# Draft_2.net
KiCad netlist of a schematic drawn in EAGLE
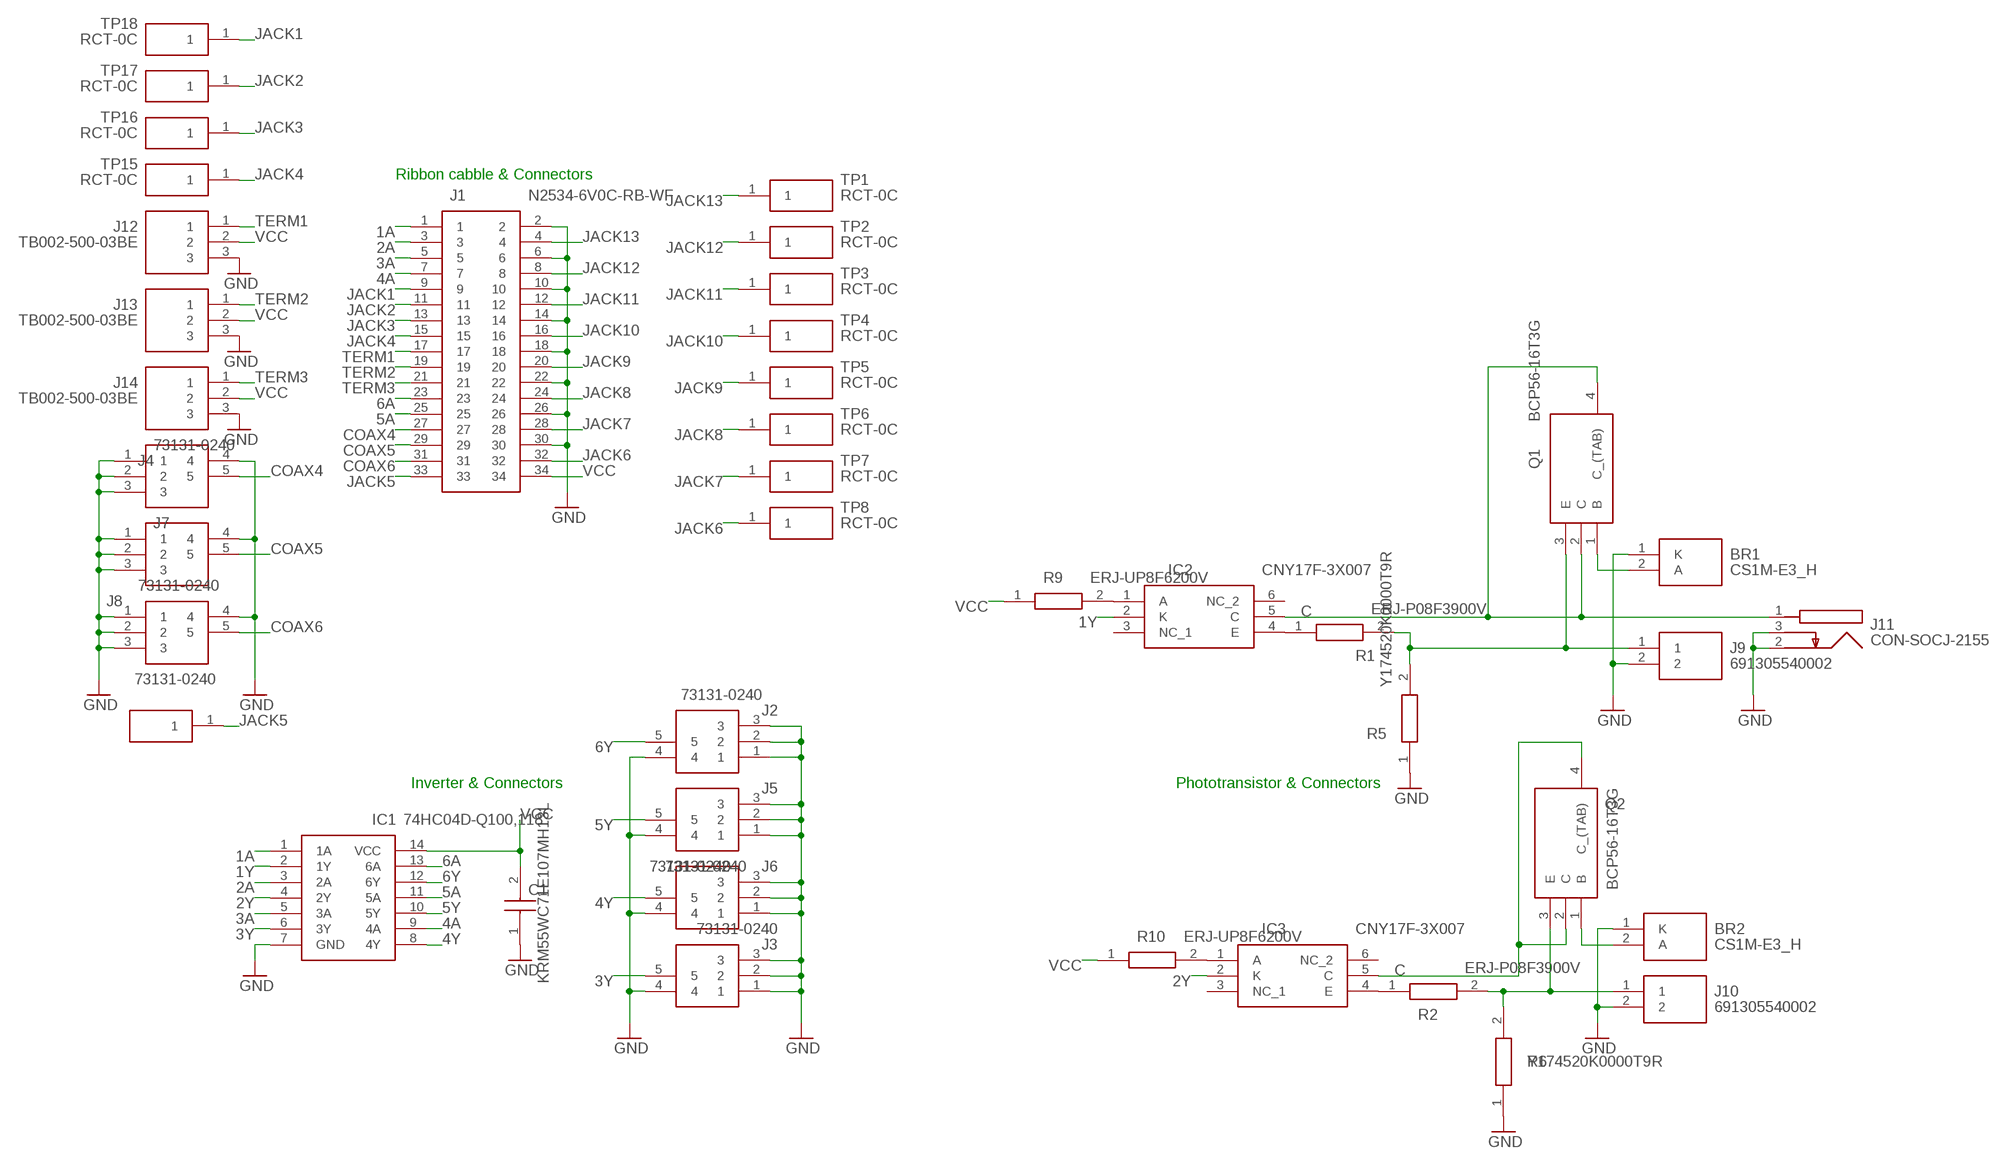
[diagram p0: schematic, sheet 1]

(export (version "E")
  (design (tool "Eeschema 10.0.6"))
  (components
    (comp (ref "BR1")
      (value "CS1M-E3_H")
      (footprint "eagle-import:DIOM5127X229N")
      (fields
        (field (name "MANUFACTURER_PART_NUMBER") "CS1M-E3/H")
        (field (name "MOUSER_PART_NUMBER") "78-CS1M-E3/H")
      )
      (libsource (lib "eagle-import") (part "CS1M-E3_H"))
    )
    (comp (ref "BR2")
      (value "CS1M-E3_H")
      (footprint "eagle-import:DIOM5127X229N")
      (fields
        (field (name "MANUFACTURER_PART_NUMBER") "CS1M-E3/H")
        (field (name "MOUSER_PART_NUMBER") "78-CS1M-E3/H")
      )
      (libsource (lib "eagle-import") (part "CS1M-E3_H"))
    )
    (comp (ref "C1")
      (value "KRM55WC71E107MH13L")
      (footprint "eagle-import:CAPC6153X670N")
      (fields (field (name "MOUSER_PART_NUMBER") "81-KRM55WC71E107MH3L"))
      (libsource (lib "eagle-import") (part "KRM55WC71E107MH13L"))
    )
    (comp (ref "IC1")
      (value "74HC04D-Q100,118")
      (footprint "eagle-import:SOIC127P600X175-14N")
      (fields (field (name "MOUSER_PART_NUMBER") "771-74HC04D-Q100"))
      (libsource (lib "eagle-import") (part "74HC04D-Q100,118"))
    )
    (comp (ref "IC2")
      (value "CNY17F-3X007")
      (footprint "eagle-import:SOP254P1030X440-6N")
      (fields (field (name "MOUSER_PART_NUMBER") "782-CNY17F-3X007"))
      (libsource (lib "eagle-import") (part "CNY17F-3X007"))
    )
    (comp (ref "IC3")
      (value "CNY17F-3X007")
      (footprint "eagle-import:SOP254P1030X440-6N")
      (fields (field (name "MOUSER_PART_NUMBER") "782-CNY17F-3X007"))
      (libsource (lib "eagle-import") (part "CNY17F-3X007"))
    )
    (comp (ref "J1")
      (value "N2534-6V0C-RB-WF")
      (footprint "eagle-import:3M_N2534-6V0C-RB-WF")
      (fields
        (field (name "MOUSER_PART_NUMBER") "517-N2534-6V0C-RB-WF")
        (field (name "RS_PART_NUMBER") "0212650")
      )
      (libsource (lib "eagle-import") (part "N2534-6V0C-RB-WF"))
    )
    (comp (ref "J2")
      (value "73131-0240")
      (footprint "eagle-import:731310240")
      (fields (field (name "MOUSER_PART_NUMBER") "538-73131-0240"))
      (libsource (lib "eagle-import") (part "73131-0240"))
    )
    (comp (ref "J3")
      (value "73131-0240")
      (footprint "eagle-import:731310240")
      (fields (field (name "MOUSER_PART_NUMBER") "538-73131-0240"))
      (libsource (lib "eagle-import") (part "73131-0240"))
    )
    (comp (ref "J4")
      (value "73131-0240")
      (footprint "eagle-import:731310240")
      (fields (field (name "MOUSER_PART_NUMBER") "538-73131-0240"))
      (libsource (lib "eagle-import") (part "73131-0240"))
    )
    (comp (ref "J5")
      (value "73131-0240")
      (footprint "eagle-import:731310240")
      (fields (field (name "MOUSER_PART_NUMBER") "538-73131-0240"))
      (libsource (lib "eagle-import") (part "73131-0240"))
    )
    (comp (ref "J6")
      (value "73131-0240")
      (footprint "eagle-import:731310240")
      (fields (field (name "MOUSER_PART_NUMBER") "538-73131-0240"))
      (libsource (lib "eagle-import") (part "73131-0240"))
    )
    (comp (ref "J7")
      (value "73131-0240")
      (footprint "eagle-import:731310240")
      (fields (field (name "MOUSER_PART_NUMBER") "538-73131-0240"))
      (libsource (lib "eagle-import") (part "73131-0240"))
    )
    (comp (ref "J8")
      (value "73131-0240")
      (footprint "eagle-import:731310240")
      (fields (field (name "MOUSER_PART_NUMBER") "538-73131-0240"))
      (libsource (lib "eagle-import") (part "73131-0240"))
    )
    (comp (ref "J9")
      (value "691305540002")
      (footprint "eagle-import:SHDRRA2W100P0X508_1X2_1216X120")
      (fields (field (name "MOUSER_PART_NUMBER") "710-691305540002"))
      (libsource (lib "eagle-import") (part "691305540002"))
    )
    (comp (ref "J10")
      (value "691305540002")
      (footprint "eagle-import:SHDRRA2W100P0X508_1X2_1216X120")
      (fields (field (name "MOUSER_PART_NUMBER") "710-691305540002"))
      (libsource (lib "eagle-import") (part "691305540002"))
    )
    (comp (ref "J11")
      (value "CON-SOCJ-2155")
      (footprint "eagle-import:CONSOCJ2155")
      (fields (field (name "MOUSER_PART_NUMBER") "992-CON-SOCJ-2155"))
      (libsource (lib "eagle-import") (part "CON-SOCJ-2155"))
    )
    (comp (ref "J12")
      (value "TB002-500-03BE")
      (footprint "eagle-import:SHDR3W100P0X500_1X3_1500X760X1")
      (fields (field (name "MOUSER_PART_NUMBER") "490-TB002-500-03BE"))
      (libsource (lib "eagle-import") (part "TB002-500-03BE"))
    )
    (comp (ref "J13")
      (value "TB002-500-03BE")
      (footprint "eagle-import:SHDR3W100P0X500_1X3_1500X760X1")
      (fields (field (name "MOUSER_PART_NUMBER") "490-TB002-500-03BE"))
      (libsource (lib "eagle-import") (part "TB002-500-03BE"))
    )
    (comp (ref "J14")
      (value "TB002-500-03BE")
      (footprint "eagle-import:SHDR3W100P0X500_1X3_1500X760X1")
      (fields (field (name "MOUSER_PART_NUMBER") "490-TB002-500-03BE"))
      (libsource (lib "eagle-import") (part "TB002-500-03BE"))
    )
    (comp (ref "Q1")
      (value "BCP56-16T3G")
      (footprint "eagle-import:SOT230P700X175-4N")
      (fields
        (field (name "MOUSER_PART_NUMBER") "863-BCP56-16T3G")
        (field (name "RS_PART_NUMBER") "7737633P")
      )
      (libsource (lib "eagle-import") (part "BCP56-16T3G"))
    )
    (comp (ref "Q2")
      (value "BCP56-16T3G")
      (footprint "eagle-import:SOT230P700X175-4N")
      (fields
        (field (name "MOUSER_PART_NUMBER") "863-BCP56-16T3G")
        (field (name "RS_PART_NUMBER") "7737633P")
      )
      (libsource (lib "eagle-import") (part "BCP56-16T3G"))
    )
    (comp (ref "R1")
      (value "ERJ-P08F3900V")
      (footprint "eagle-import:RESC3116X70N")
      (fields (field (name "MOUSER_PART_NUMBER") "667-ERJ-P08F3900V"))
      (libsource (lib "eagle-import") (part "ERJ-P08F3900V"))
    )
    (comp (ref "R2")
      (value "ERJ-P08F3900V")
      (footprint "eagle-import:RESC3116X70N")
      (fields (field (name "MOUSER_PART_NUMBER") "667-ERJ-P08F3900V"))
      (libsource (lib "eagle-import") (part "ERJ-P08F3900V"))
    )
    (comp (ref "R5")
      (value "Y174520K0000T9R")
      (footprint "eagle-import:RESM6032X279N")
      (fields
        (field (name "MOUSER_PART_NUMBER") "71-SMR1DZ20K000TST")
        (field (name "RS_PART_NUMBER") "7637249P")
      )
      (libsource (lib "eagle-import") (part "Y174520K0000T9R"))
    )
    (comp (ref "R6")
      (value "Y174520K0000T9R")
      (footprint "eagle-import:RESM6032X279N")
      (fields
        (field (name "MOUSER_PART_NUMBER") "71-SMR1DZ20K000TST")
        (field (name "RS_PART_NUMBER") "7637249P")
      )
      (libsource (lib "eagle-import") (part "Y174520K0000T9R"))
    )
    (comp (ref "R9")
      (value "ERJ-UP8F6200V")
      (footprint "eagle-import:RESC3116X70N")
      (fields (field (name "MOUSER_PART_NUMBER") "667-ERJ-UP8F6200V"))
      (libsource (lib "eagle-import") (part "ERJ-UP8F6200V"))
    )
    (comp (ref "R10")
      (value "ERJ-UP8F6200V")
      (footprint "eagle-import:RESC3116X70N")
      (fields (field (name "MOUSER_PART_NUMBER") "667-ERJ-UP8F6200V"))
      (libsource (lib "eagle-import") (part "ERJ-UP8F6200V"))
    )
    (comp (ref "TP1")
      (value "RCT-0C")
      (footprint "eagle-import:RCT-0C")
      (fields (field (name "MOUSER_PART_NUMBER") "279-RCT-0C"))
      (libsource (lib "eagle-import") (part "RCT-0C"))
    )
    (comp (ref "TP2")
      (value "RCT-0C")
      (footprint "eagle-import:RCT-0C")
      (fields (field (name "MOUSER_PART_NUMBER") "279-RCT-0C"))
      (libsource (lib "eagle-import") (part "RCT-0C"))
    )
    (comp (ref "TP3")
      (value "RCT-0C")
      (footprint "eagle-import:RCT-0C")
      (fields (field (name "MOUSER_PART_NUMBER") "279-RCT-0C"))
      (libsource (lib "eagle-import") (part "RCT-0C"))
    )
    (comp (ref "TP4")
      (value "RCT-0C")
      (footprint "eagle-import:RCT-0C")
      (fields (field (name "MOUSER_PART_NUMBER") "279-RCT-0C"))
      (libsource (lib "eagle-import") (part "RCT-0C"))
    )
    (comp (ref "TP5")
      (value "RCT-0C")
      (footprint "eagle-import:RCT-0C")
      (fields (field (name "MOUSER_PART_NUMBER") "279-RCT-0C"))
      (libsource (lib "eagle-import") (part "RCT-0C"))
    )
    (comp (ref "TP6")
      (value "RCT-0C")
      (footprint "eagle-import:RCT-0C")
      (fields (field (name "MOUSER_PART_NUMBER") "279-RCT-0C"))
      (libsource (lib "eagle-import") (part "RCT-0C"))
    )
    (comp (ref "TP7")
      (value "RCT-0C")
      (footprint "eagle-import:RCT-0C")
      (fields (field (name "MOUSER_PART_NUMBER") "279-RCT-0C"))
      (libsource (lib "eagle-import") (part "RCT-0C"))
    )
    (comp (ref "TP8")
      (value "RCT-0C")
      (footprint "eagle-import:RCT-0C")
      (fields (field (name "MOUSER_PART_NUMBER") "279-RCT-0C"))
      (libsource (lib "eagle-import") (part "RCT-0C"))
    )
    (comp (ref "TP9")
      (value "RCT-0C")
      (footprint "eagle-import:RCT-0C")
      (fields (field (name "MOUSER_PART_NUMBER") "279-RCT-0C"))
      (libsource (lib "eagle-import") (part "RCT-0C"))
    )
    (comp (ref "TP15")
      (value "RCT-0C")
      (footprint "eagle-import:RCT-0C")
      (fields (field (name "MOUSER_PART_NUMBER") "279-RCT-0C"))
      (libsource (lib "eagle-import") (part "RCT-0C"))
    )
    (comp (ref "TP16")
      (value "RCT-0C")
      (footprint "eagle-import:RCT-0C")
      (fields (field (name "MOUSER_PART_NUMBER") "279-RCT-0C"))
      (libsource (lib "eagle-import") (part "RCT-0C"))
    )
    (comp (ref "TP17")
      (value "RCT-0C")
      (footprint "eagle-import:RCT-0C")
      (fields (field (name "MOUSER_PART_NUMBER") "279-RCT-0C"))
      (libsource (lib "eagle-import") (part "RCT-0C"))
    )
    (comp (ref "TP18")
      (value "RCT-0C")
      (footprint "eagle-import:RCT-0C")
      (fields (field (name "MOUSER_PART_NUMBER") "279-RCT-0C"))
      (libsource (lib "eagle-import") (part "RCT-0C"))
    )
  )
  (nets
    (net (code "1") (name "/1A") (class "Default")
      (node (ref "IC1") (pin "1") (pinfunction "1A_1") (pintype "bidirectional"))
      (node (ref "J1") (pin "1") (pinfunction "1_1") (pintype "bidirectional"))
    )
    (net (code "2") (name "/1Y") (class "Default")
      (node (ref "IC1") (pin "2") (pinfunction "1Y_2") (pintype "bidirectional"))
      (node (ref "IC2") (pin "2") (pinfunction "K_2") (pintype "bidirectional"))
    )
    (net (code "3") (name "/2A") (class "Default")
      (node (ref "IC1") (pin "3") (pinfunction "2A_3") (pintype "bidirectional"))
      (node (ref "J1") (pin "3") (pinfunction "3_3") (pintype "bidirectional"))
    )
    (net (code "4") (name "/2Y") (class "Default")
      (node (ref "IC1") (pin "4") (pinfunction "2Y_4") (pintype "bidirectional"))
      (node (ref "IC3") (pin "2") (pinfunction "K_2") (pintype "bidirectional"))
    )
    (net (code "5") (name "/3A") (class "Default")
      (node (ref "IC1") (pin "5") (pinfunction "3A_5") (pintype "bidirectional"))
      (node (ref "J1") (pin "5") (pinfunction "5_5") (pintype "bidirectional"))
    )
    (net (code "6") (name "/3Y") (class "Default")
      (node (ref "IC1") (pin "6") (pinfunction "3Y_6") (pintype "bidirectional"))
      (node (ref "J3") (pin "5") (pinfunction "5_5") (pintype "bidirectional"))
    )
    (net (code "7") (name "/4A") (class "Default")
      (node (ref "IC1") (pin "9") (pinfunction "4A_9") (pintype "bidirectional"))
      (node (ref "J1") (pin "7") (pinfunction "7_7") (pintype "bidirectional"))
    )
    (net (code "8") (name "/4Y") (class "Default")
      (node (ref "IC1") (pin "8") (pinfunction "4Y_8") (pintype "bidirectional"))
      (node (ref "J6") (pin "5") (pinfunction "5_5") (pintype "bidirectional"))
    )
    (net (code "9") (name "/5A") (class "Default")
      (node (ref "IC1") (pin "11") (pinfunction "5A_11") (pintype "bidirectional"))
      (node (ref "J1") (pin "25") (pinfunction "25_25") (pintype "bidirectional"))
    )
    (net (code "10") (name "/5Y") (class "Default")
      (node (ref "IC1") (pin "10") (pinfunction "5Y_10") (pintype "bidirectional"))
      (node (ref "J5") (pin "5") (pinfunction "5_5") (pintype "bidirectional"))
    )
    (net (code "11") (name "/6A") (class "Default")
      (node (ref "IC1") (pin "13") (pinfunction "6A_13") (pintype "bidirectional"))
      (node (ref "J1") (pin "23") (pinfunction "23_23") (pintype "bidirectional"))
    )
    (net (code "12") (name "/6Y") (class "Default")
      (node (ref "IC1") (pin "12") (pinfunction "6Y_12") (pintype "bidirectional"))
      (node (ref "J2") (pin "5") (pinfunction "5_5") (pintype "bidirectional"))
    )
    (net (code "13") (name "/C") (class "Default")
      (node (ref "IC2") (pin "5") (pinfunction "C_5") (pintype "bidirectional"))
      (node (ref "IC3") (pin "5") (pinfunction "C_5") (pintype "bidirectional"))
      (node (ref "J11") (pin "1") (pinfunction "1_1") (pintype "bidirectional"))
      (node (ref "Q1") (pin "2") (pinfunction "C_2") (pintype "bidirectional"))
      (node (ref "Q1") (pin "4") (pinfunction "C_(TAB)_4") (pintype "bidirectional"))
      (node (ref "Q2") (pin "2") (pinfunction "C_2") (pintype "bidirectional"))
      (node (ref "Q2") (pin "4") (pinfunction "C_(TAB)_4") (pintype "bidirectional"))
    )
    (net (code "14") (name "/COAX4") (class "Default")
      (node (ref "J1") (pin "27") (pinfunction "27_27") (pintype "bidirectional"))
      (node (ref "J4") (pin "5") (pinfunction "5_5") (pintype "bidirectional"))
    )
    (net (code "15") (name "/COAX5") (class "Default")
      (node (ref "J1") (pin "29") (pinfunction "29_29") (pintype "bidirectional"))
      (node (ref "J7") (pin "5") (pinfunction "5_5") (pintype "bidirectional"))
    )
    (net (code "16") (name "/COAX6") (class "Default")
      (node (ref "J1") (pin "31") (pinfunction "31_31") (pintype "bidirectional"))
      (node (ref "J8") (pin "5") (pinfunction "5_5") (pintype "bidirectional"))
    )
    (net (code "17") (name "/JACK1") (class "Default")
      (node (ref "J1") (pin "9") (pinfunction "9_9") (pintype "bidirectional"))
      (node (ref "TP18") (pin "1") (pinfunction "1_1") (pintype "bidirectional"))
    )
    (net (code "18") (name "/JACK2") (class "Default")
      (node (ref "J1") (pin "11") (pinfunction "11_11") (pintype "bidirectional"))
      (node (ref "TP17") (pin "1") (pinfunction "1_1") (pintype "bidirectional"))
    )
    (net (code "19") (name "/JACK3") (class "Default")
      (node (ref "J1") (pin "13") (pinfunction "13_13") (pintype "bidirectional"))
      (node (ref "TP16") (pin "1") (pinfunction "1_1") (pintype "bidirectional"))
    )
    (net (code "20") (name "/JACK4") (class "Default")
      (node (ref "J1") (pin "15") (pinfunction "15_15") (pintype "bidirectional"))
      (node (ref "TP15") (pin "1") (pinfunction "1_1") (pintype "bidirectional"))
    )
    (net (code "21") (name "/JACK5") (class "Default")
      (node (ref "J1") (pin "33") (pinfunction "33_33") (pintype "bidirectional"))
      (node (ref "TP9") (pin "1") (pinfunction "1_1") (pintype "bidirectional"))
    )
    (net (code "22") (name "/JACK6") (class "Default")
      (node (ref "J1") (pin "32") (pinfunction "32_32") (pintype "bidirectional"))
      (node (ref "TP8") (pin "1") (pinfunction "1_1") (pintype "bidirectional"))
    )
    (net (code "23") (name "/JACK7") (class "Default")
      (node (ref "J1") (pin "28") (pinfunction "28_28") (pintype "bidirectional"))
      (node (ref "TP7") (pin "1") (pinfunction "1_1") (pintype "bidirectional"))
    )
    (net (code "24") (name "/JACK8") (class "Default")
      (node (ref "J1") (pin "24") (pinfunction "24_24") (pintype "bidirectional"))
      (node (ref "TP6") (pin "1") (pinfunction "1_1") (pintype "bidirectional"))
    )
    (net (code "25") (name "/JACK9") (class "Default")
      (node (ref "J1") (pin "20") (pinfunction "20_20") (pintype "bidirectional"))
      (node (ref "TP5") (pin "1") (pinfunction "1_1") (pintype "bidirectional"))
    )
    (net (code "26") (name "/JACK10") (class "Default")
      (node (ref "J1") (pin "16") (pinfunction "16_16") (pintype "bidirectional"))
      (node (ref "TP4") (pin "1") (pinfunction "1_1") (pintype "bidirectional"))
    )
    (net (code "27") (name "/JACK11") (class "Default")
      (node (ref "J1") (pin "12") (pinfunction "12_12") (pintype "bidirectional"))
      (node (ref "TP3") (pin "1") (pinfunction "1_1") (pintype "bidirectional"))
    )
    (net (code "28") (name "/JACK12") (class "Default")
      (node (ref "J1") (pin "8") (pinfunction "8_8") (pintype "bidirectional"))
      (node (ref "TP2") (pin "1") (pinfunction "1_1") (pintype "bidirectional"))
    )
    (net (code "29") (name "/JACK13") (class "Default")
      (node (ref "J1") (pin "4") (pinfunction "4_4") (pintype "bidirectional"))
      (node (ref "TP1") (pin "1") (pinfunction "1_1") (pintype "bidirectional"))
    )
    (net (code "30") (name "/TERM1") (class "Default")
      (node (ref "J1") (pin "17") (pinfunction "17_17") (pintype "bidirectional"))
      (node (ref "J12") (pin "1") (pinfunction "1_1") (pintype "bidirectional"))
    )
    (net (code "31") (name "/TERM2") (class "Default")
      (node (ref "J1") (pin "19") (pinfunction "19_19") (pintype "bidirectional"))
      (node (ref "J13") (pin "1") (pinfunction "1_1") (pintype "bidirectional"))
    )
    (net (code "32") (name "/TERM3") (class "Default")
      (node (ref "J1") (pin "21") (pinfunction "21_21") (pintype "bidirectional"))
      (node (ref "J14") (pin "1") (pinfunction "1_1") (pintype "bidirectional"))
    )
    (net (code "33") (name "/VCC") (class "Default")
      (node (ref "C1") (pin "2") (pinfunction "2_2") (pintype "bidirectional"))
      (node (ref "IC1") (pin "14") (pinfunction "VCC_14") (pintype "bidirectional"))
      (node (ref "J1") (pin "34") (pinfunction "34_34") (pintype "bidirectional"))
      (node (ref "J12") (pin "2") (pinfunction "2_2") (pintype "bidirectional"))
      (node (ref "J13") (pin "2") (pinfunction "2_2") (pintype "bidirectional"))
      (node (ref "J14") (pin "2") (pinfunction "2_2") (pintype "bidirectional"))
      (node (ref "R10") (pin "1") (pinfunction "1_1") (pintype "bidirectional"))
      (node (ref "R9") (pin "1") (pinfunction "1_1") (pintype "bidirectional"))
    )
    (net (code "34") (name "GND") (class "Default")
      (node (ref "BR1") (pin "1") (pinfunction "K_1") (pintype "bidirectional"))
      (node (ref "BR2") (pin "1") (pinfunction "K_1") (pintype "bidirectional"))
      (node (ref "C1") (pin "1") (pinfunction "1_1") (pintype "bidirectional"))
      (node (ref "IC1") (pin "7") (pinfunction "GND_7") (pintype "bidirectional"))
      (node (ref "J1") (pin "10") (pinfunction "10_10") (pintype "bidirectional"))
      (node (ref "J1") (pin "14") (pinfunction "14_14") (pintype "bidirectional"))
      (node (ref "J1") (pin "18") (pinfunction "18_18") (pintype "bidirectional"))
      (node (ref "J1") (pin "2") (pinfunction "2_2") (pintype "bidirectional"))
      (node (ref "J1") (pin "22") (pinfunction "22_22") (pintype "bidirectional"))
      (node (ref "J1") (pin "26") (pinfunction "26_26") (pintype "bidirectional"))
      (node (ref "J1") (pin "30") (pinfunction "30_30") (pintype "bidirectional"))
      (node (ref "J1") (pin "6") (pinfunction "6_6") (pintype "bidirectional"))
      (node (ref "J10") (pin "2") (pinfunction "2_2") (pintype "bidirectional"))
      (node (ref "J11") (pin "2") (pinfunction "2_2") (pintype "bidirectional"))
      (node (ref "J11") (pin "3") (pinfunction "3_3") (pintype "bidirectional"))
      (node (ref "J12") (pin "3") (pinfunction "3_3") (pintype "bidirectional"))
      (node (ref "J13") (pin "3") (pinfunction "3_3") (pintype "bidirectional"))
      (node (ref "J14") (pin "3") (pinfunction "3_3") (pintype "bidirectional"))
      (node (ref "J2") (pin "1") (pinfunction "1_1") (pintype "bidirectional"))
      (node (ref "J2") (pin "2") (pinfunction "2_2") (pintype "bidirectional"))
      (node (ref "J2") (pin "3") (pinfunction "3_3") (pintype "bidirectional"))
      (node (ref "J2") (pin "4") (pinfunction "4_4") (pintype "bidirectional"))
      (node (ref "J3") (pin "1") (pinfunction "1_1") (pintype "bidirectional"))
      (node (ref "J3") (pin "2") (pinfunction "2_2") (pintype "bidirectional"))
      (node (ref "J3") (pin "3") (pinfunction "3_3") (pintype "bidirectional"))
      (node (ref "J3") (pin "4") (pinfunction "4_4") (pintype "bidirectional"))
      (node (ref "J4") (pin "1") (pinfunction "1_1") (pintype "bidirectional"))
      (node (ref "J4") (pin "2") (pinfunction "2_2") (pintype "bidirectional"))
      (node (ref "J4") (pin "3") (pinfunction "3_3") (pintype "bidirectional"))
      (node (ref "J4") (pin "4") (pinfunction "4_4") (pintype "bidirectional"))
      (node (ref "J5") (pin "1") (pinfunction "1_1") (pintype "bidirectional"))
      (node (ref "J5") (pin "2") (pinfunction "2_2") (pintype "bidirectional"))
      (node (ref "J5") (pin "3") (pinfunction "3_3") (pintype "bidirectional"))
      (node (ref "J5") (pin "4") (pinfunction "4_4") (pintype "bidirectional"))
      (node (ref "J6") (pin "1") (pinfunction "1_1") (pintype "bidirectional"))
      (node (ref "J6") (pin "2") (pinfunction "2_2") (pintype "bidirectional"))
      (node (ref "J6") (pin "3") (pinfunction "3_3") (pintype "bidirectional"))
      (node (ref "J6") (pin "4") (pinfunction "4_4") (pintype "bidirectional"))
      (node (ref "J7") (pin "1") (pinfunction "1_1") (pintype "bidirectional"))
      (node (ref "J7") (pin "2") (pinfunction "2_2") (pintype "bidirectional"))
      (node (ref "J7") (pin "3") (pinfunction "3_3") (pintype "bidirectional"))
      (node (ref "J7") (pin "4") (pinfunction "4_4") (pintype "bidirectional"))
      (node (ref "J8") (pin "1") (pinfunction "1_1") (pintype "bidirectional"))
      (node (ref "J8") (pin "2") (pinfunction "2_2") (pintype "bidirectional"))
      (node (ref "J8") (pin "3") (pinfunction "3_3") (pintype "bidirectional"))
      (node (ref "J8") (pin "4") (pinfunction "4_4") (pintype "bidirectional"))
      (node (ref "J9") (pin "2") (pinfunction "2_2") (pintype "bidirectional"))
      (node (ref "R5") (pin "1") (pinfunction "1_1") (pintype "bidirectional"))
      (node (ref "R6") (pin "1") (pinfunction "1_1") (pintype "bidirectional"))
    )
    (net (code "35") (name "Net-(BR1-A)") (class "Default")
      (node (ref "BR1") (pin "2") (pinfunction "A_2") (pintype "bidirectional"))
      (node (ref "Q1") (pin "1") (pinfunction "B_1") (pintype "bidirectional"))
    )
    (net (code "36") (name "Net-(BR2-A)") (class "Default")
      (node (ref "BR2") (pin "2") (pinfunction "A_2") (pintype "bidirectional"))
      (node (ref "Q2") (pin "1") (pinfunction "B_1") (pintype "bidirectional"))
    )
    (net (code "37") (name "Net-(IC2-A)") (class "Default")
      (node (ref "IC2") (pin "1") (pinfunction "A_1") (pintype "bidirectional"))
      (node (ref "R9") (pin "2") (pinfunction "2_2") (pintype "bidirectional"))
    )
    (net (code "38") (name "Net-(IC2-E)") (class "Default")
      (node (ref "IC2") (pin "4") (pinfunction "E_4") (pintype "bidirectional"))
      (node (ref "R1") (pin "1") (pinfunction "1_1") (pintype "bidirectional"))
    )
    (net (code "39") (name "Net-(IC3-A)") (class "Default")
      (node (ref "IC3") (pin "1") (pinfunction "A_1") (pintype "bidirectional"))
      (node (ref "R10") (pin "2") (pinfunction "2_2") (pintype "bidirectional"))
    )
    (net (code "40") (name "Net-(IC3-E)") (class "Default")
      (node (ref "IC3") (pin "4") (pinfunction "E_4") (pintype "bidirectional"))
      (node (ref "R2") (pin "1") (pinfunction "1_1") (pintype "bidirectional"))
    )
    (net (code "41") (name "Net-(Q1-E)") (class "Default")
      (node (ref "J9") (pin "1") (pinfunction "1_1") (pintype "bidirectional"))
      (node (ref "Q1") (pin "3") (pinfunction "E_3") (pintype "bidirectional"))
      (node (ref "R1") (pin "2") (pinfunction "2_2") (pintype "bidirectional"))
      (node (ref "R5") (pin "2") (pinfunction "2_2") (pintype "bidirectional"))
    )
    (net (code "42") (name "Net-(Q2-E)") (class "Default")
      (node (ref "J10") (pin "1") (pinfunction "1_1") (pintype "bidirectional"))
      (node (ref "Q2") (pin "3") (pinfunction "E_3") (pintype "bidirectional"))
      (node (ref "R2") (pin "2") (pinfunction "2_2") (pintype "bidirectional"))
      (node (ref "R6") (pin "2") (pinfunction "2_2") (pintype "bidirectional"))
    )
    (net (code "43") (name "unconnected-(IC2-NC_1-Pad3)") (class "Default")
      (node (ref "IC2") (pin "3") (pinfunction "NC_1_3") (pintype "bidirectional"))
    )
    (net (code "44") (name "unconnected-(IC2-NC_2-Pad6)") (class "Default")
      (node (ref "IC2") (pin "6") (pinfunction "NC_2_6") (pintype "bidirectional"))
    )
    (net (code "45") (name "unconnected-(IC3-NC_1-Pad3)") (class "Default")
      (node (ref "IC3") (pin "3") (pinfunction "NC_1_3") (pintype "bidirectional"))
    )
    (net (code "46") (name "unconnected-(IC3-NC_2-Pad6)") (class "Default")
      (node (ref "IC3") (pin "6") (pinfunction "NC_2_6") (pintype "bidirectional"))
    )
  )
)
